# 20W-IR-Blaster.net
KiCad netlist of a schematic drawn in EAGLE
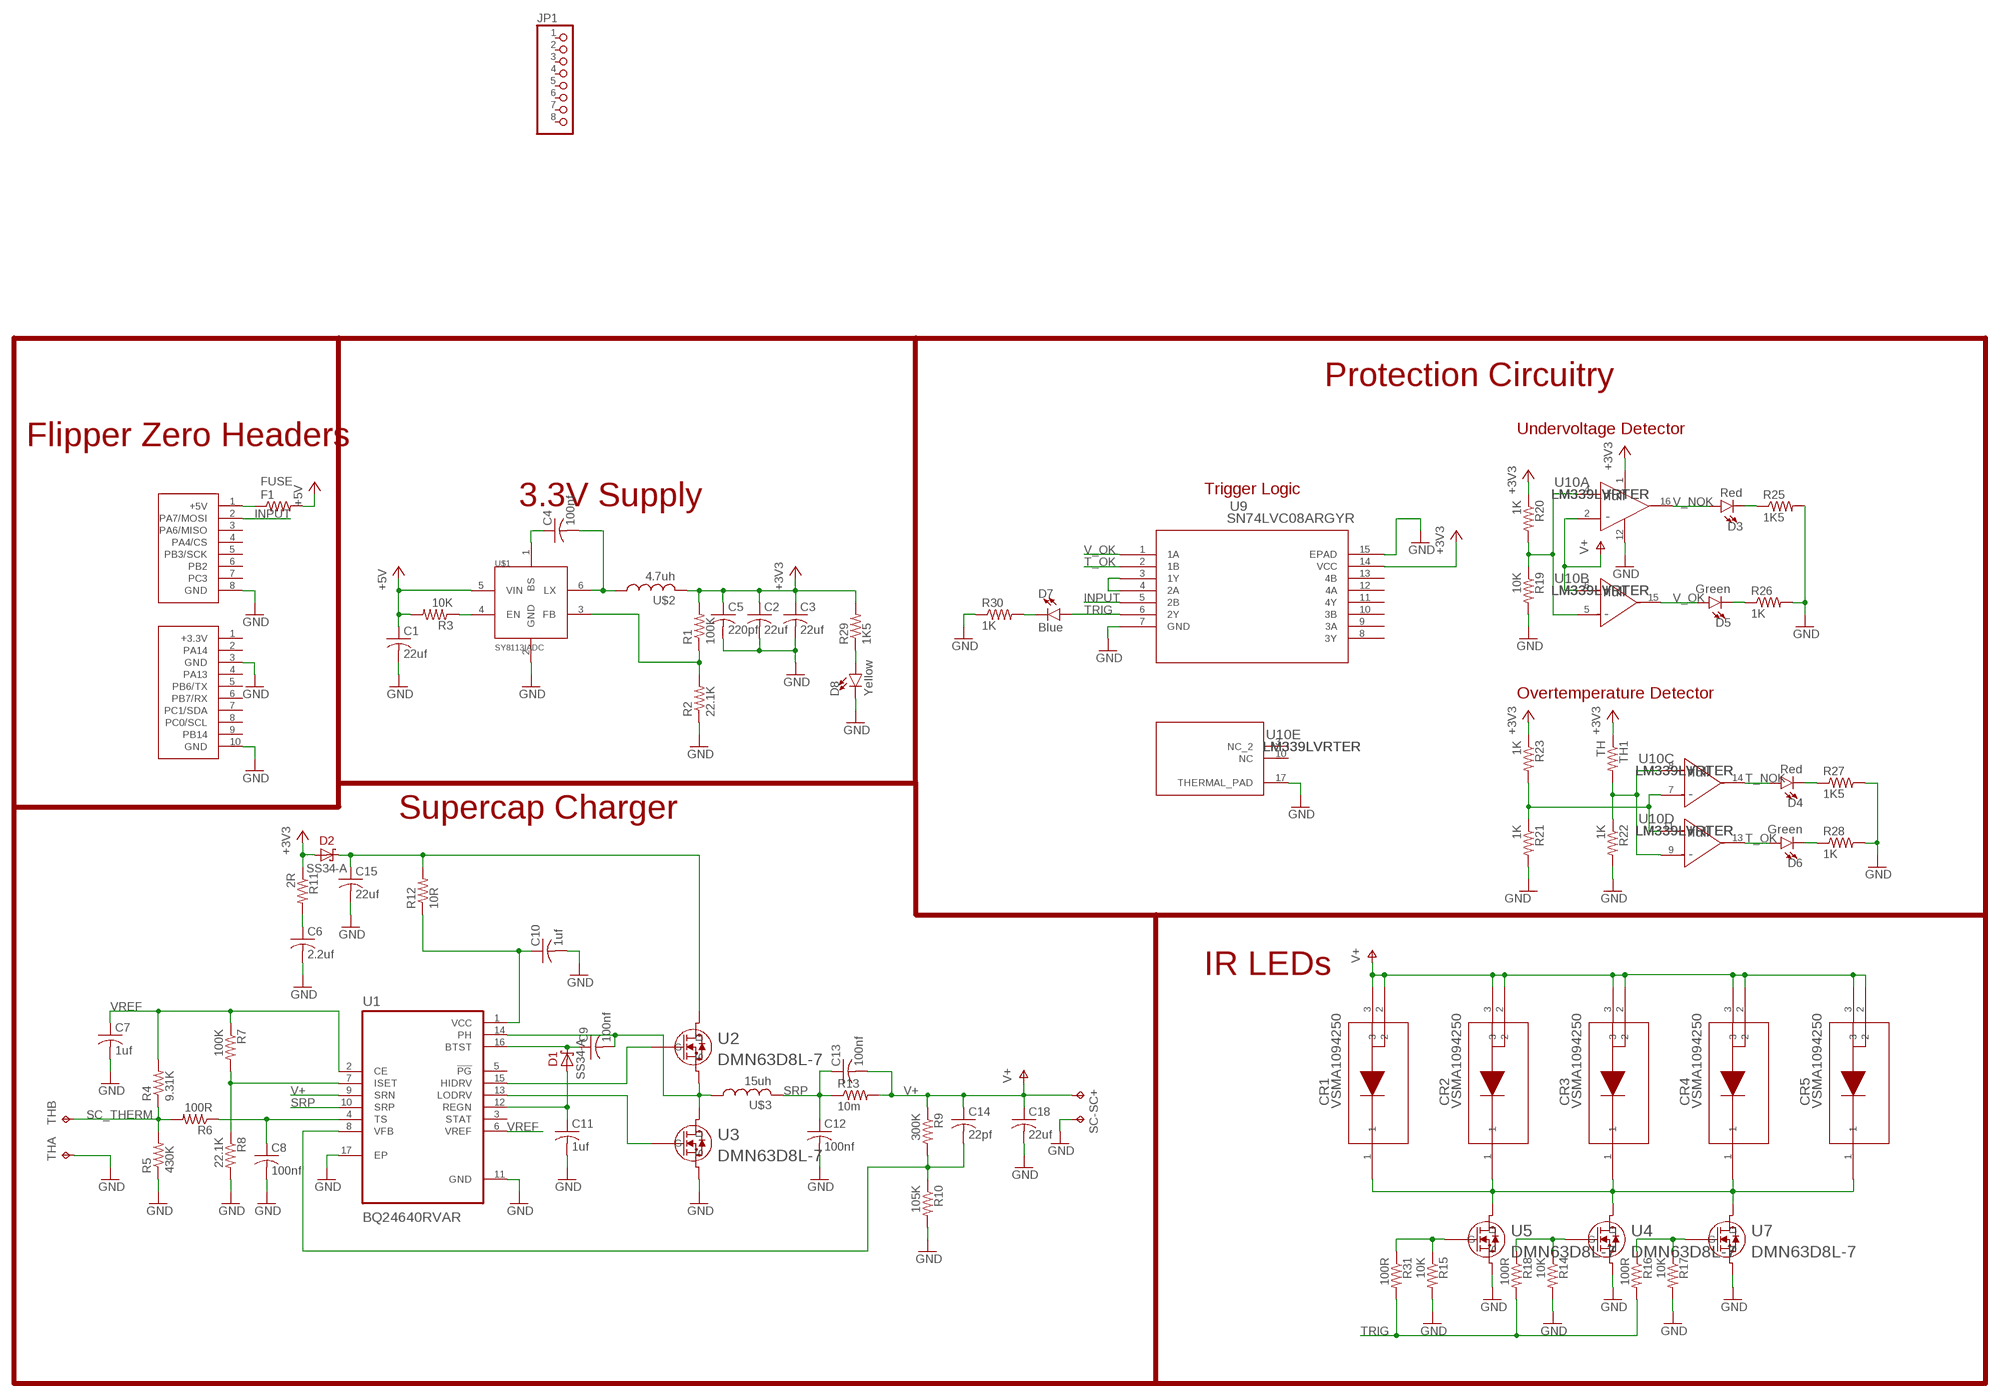
[diagram p0: schematic, sheet 1]

(export (version "E")
  (design (tool "Eeschema 10.0.6"))
  (components
    (comp (ref "C1")
      (value "22uf")
      (footprint "eagle-import:C3216")
      (libsource (lib "eagle-import") (part "C-USC3216"))
    )
    (comp (ref "C2")
      (value "22uf")
      (footprint "eagle-import:C3216")
      (libsource (lib "eagle-import") (part "C-USC3216"))
    )
    (comp (ref "C3")
      (value "22uf")
      (footprint "eagle-import:C3216")
      (libsource (lib "eagle-import") (part "C-USC3216"))
    )
    (comp (ref "C4")
      (value "100nf")
      (footprint "eagle-import:C0603")
      (libsource (lib "eagle-import") (part "C-USC0603"))
    )
    (comp (ref "C5")
      (value "220pf")
      (footprint "eagle-import:C0603")
      (libsource (lib "eagle-import") (part "C-USC0603"))
    )
    (comp (ref "C6")
      (value "2.2uf")
      (footprint "eagle-import:C0603")
      (libsource (lib "eagle-import") (part "C-USC0603"))
    )
    (comp (ref "C7")
      (value "1uf")
      (footprint "eagle-import:C0603")
      (libsource (lib "eagle-import") (part "C-USC0603"))
    )
    (comp (ref "C8")
      (value "100nf")
      (footprint "eagle-import:C0603")
      (libsource (lib "eagle-import") (part "C-USC0603"))
    )
    (comp (ref "C9")
      (value "100nf")
      (footprint "eagle-import:C0603")
      (libsource (lib "eagle-import") (part "C-USC0603"))
    )
    (comp (ref "C10")
      (value "1uf")
      (footprint "eagle-import:C0603")
      (libsource (lib "eagle-import") (part "C-USC0603"))
    )
    (comp (ref "C11")
      (value "1uf")
      (footprint "eagle-import:C0603")
      (libsource (lib "eagle-import") (part "C-USC0603"))
    )
    (comp (ref "C12")
      (value "100nf")
      (footprint "eagle-import:C0603")
      (libsource (lib "eagle-import") (part "C-USC0603"))
    )
    (comp (ref "C13")
      (value "100nf")
      (footprint "eagle-import:C0603")
      (libsource (lib "eagle-import") (part "C-USC0603"))
    )
    (comp (ref "C14")
      (value "22pf")
      (footprint "eagle-import:C0603")
      (libsource (lib "eagle-import") (part "C-USC0603"))
    )
    (comp (ref "C15")
      (value "22uf")
      (footprint "eagle-import:C3216")
      (libsource (lib "eagle-import") (part "C-USC3216"))
    )
    (comp (ref "C18")
      (value "22uf")
      (footprint "eagle-import:C3216")
      (libsource (lib "eagle-import") (part "C-USC3216"))
    )
    (comp (ref "CR1")
      (value "VSMA1094250")
      (footprint "eagle-import:DIODE_VSMA1094250_VIS")
      (fields (field (name "COPYRIGHT") "Copyright (C) 2025 Ultra Librarian. All rights reserved."))
      (libsource (lib "eagle-import") (part "VSMA1094250"))
    )
    (comp (ref "CR2")
      (value "VSMA1094250")
      (footprint "eagle-import:DIODE_VSMA1094250_VIS")
      (fields (field (name "COPYRIGHT") "Copyright (C) 2025 Ultra Librarian. All rights reserved."))
      (libsource (lib "eagle-import") (part "VSMA1094250"))
    )
    (comp (ref "CR3")
      (value "VSMA1094250")
      (footprint "eagle-import:DIODE_VSMA1094250_VIS")
      (fields (field (name "COPYRIGHT") "Copyright (C) 2025 Ultra Librarian. All rights reserved."))
      (libsource (lib "eagle-import") (part "VSMA1094250"))
    )
    (comp (ref "CR4")
      (value "VSMA1094250")
      (footprint "eagle-import:DIODE_VSMA1094250_VIS")
      (fields (field (name "COPYRIGHT") "Copyright (C) 2025 Ultra Librarian. All rights reserved."))
      (libsource (lib "eagle-import") (part "VSMA1094250"))
    )
    (comp (ref "CR5")
      (value "VSMA1094250")
      (footprint "eagle-import:DIODE_VSMA1094250_VIS")
      (fields (field (name "COPYRIGHT") "Copyright (C) 2025 Ultra Librarian. All rights reserved."))
      (libsource (lib "eagle-import") (part "VSMA1094250"))
    )
    (comp (ref "D1")
      (value "SS34-A")
      (footprint "eagle-import:DO-214AC")
      (fields (field (name "MF") "TE Connectivity") (field (name "MP") "SS34A"))
      (libsource (lib "eagle-import") (part "SS34-A"))
    )
    (comp (ref "D2")
      (value "SS34-A")
      (footprint "eagle-import:DO-214AC")
      (fields (field (name "MF") "TE Connectivity") (field (name "MP") "SS34A"))
      (libsource (lib "eagle-import") (part "SS34-A"))
    )
    (comp (ref "D3")
      (value "Red")
      (footprint "eagle-import:LED-0603")
      (libsource (lib "eagle-import") (part "LED-RED0603"))
    )
    (comp (ref "D4")
      (value "Red")
      (footprint "eagle-import:LED-0603")
      (libsource (lib "eagle-import") (part "LED-RED0603"))
    )
    (comp (ref "D5")
      (value "Green")
      (footprint "eagle-import:LED-0603")
      (libsource (lib "eagle-import") (part "LED-GREEN0603"))
    )
    (comp (ref "D6")
      (value "Green")
      (footprint "eagle-import:LED-0603")
      (libsource (lib "eagle-import") (part "LED-GREEN0603"))
    )
    (comp (ref "D7")
      (value "Blue")
      (footprint "eagle-import:LED-0603")
      (libsource (lib "eagle-import") (part "LED-BLUE0603"))
    )
    (comp (ref "D8")
      (value "Yellow")
      (footprint "eagle-import:LED-0603")
      (libsource (lib "eagle-import") (part "LED-YELLOW0603"))
    )
    (comp (ref "F1")
      (value "FUSE")
      (footprint "eagle-import:R1206")
      (libsource (lib "eagle-import") (part "R-US_R1206"))
    )
    (comp (ref "JP1")
      (value "PINHD-1X8")
      (footprint "eagle-import:1X08")
      (libsource (lib "eagle-import") (part "PINHD-1X8"))
    )
    (comp (ref "R1")
      (value "100K")
      (footprint "eagle-import:R0603")
      (libsource (lib "eagle-import") (part "R-US_R0603"))
    )
    (comp (ref "R2")
      (value "22.1K")
      (footprint "eagle-import:R0603")
      (libsource (lib "eagle-import") (part "R-US_R0603"))
    )
    (comp (ref "R3")
      (value "10K")
      (footprint "eagle-import:R0603")
      (libsource (lib "eagle-import") (part "R-US_R0603"))
    )
    (comp (ref "R4")
      (value "9.31K")
      (footprint "eagle-import:R0603")
      (libsource (lib "eagle-import") (part "R-US_R0603"))
    )
    (comp (ref "R5")
      (value "430K")
      (footprint "eagle-import:R0603")
      (libsource (lib "eagle-import") (part "R-US_R0603"))
    )
    (comp (ref "R6")
      (value "100R")
      (footprint "eagle-import:R0603")
      (libsource (lib "eagle-import") (part "R-US_R0603"))
    )
    (comp (ref "R7")
      (value "100K")
      (footprint "eagle-import:R0603")
      (libsource (lib "eagle-import") (part "R-US_R0603"))
    )
    (comp (ref "R8")
      (value "22.1K")
      (footprint "eagle-import:R0603")
      (libsource (lib "eagle-import") (part "R-US_R0603"))
    )
    (comp (ref "R9")
      (value "300K")
      (footprint "eagle-import:R0603")
      (libsource (lib "eagle-import") (part "R-US_R0603"))
    )
    (comp (ref "R10")
      (value "105K")
      (footprint "eagle-import:R0603")
      (libsource (lib "eagle-import") (part "R-US_R0603"))
    )
    (comp (ref "R11")
      (value "2R")
      (footprint "eagle-import:R2512")
      (libsource (lib "eagle-import") (part "R-US_R2512"))
    )
    (comp (ref "R12")
      (value "10R")
      (footprint "eagle-import:R2512")
      (libsource (lib "eagle-import") (part "R-US_R2512"))
    )
    (comp (ref "R13")
      (value "10m")
      (footprint "eagle-import:R0805")
      (libsource (lib "eagle-import") (part "R-US_R0805"))
    )
    (comp (ref "R14")
      (value "10K")
      (footprint "eagle-import:R0603")
      (libsource (lib "eagle-import") (part "R-US_R0603"))
    )
    (comp (ref "R15")
      (value "10K")
      (footprint "eagle-import:R0603")
      (libsource (lib "eagle-import") (part "R-US_R0603"))
    )
    (comp (ref "R16")
      (value "100R")
      (footprint "eagle-import:R0603")
      (libsource (lib "eagle-import") (part "R-US_R0603"))
    )
    (comp (ref "R17")
      (value "10K")
      (footprint "eagle-import:R0603")
      (libsource (lib "eagle-import") (part "R-US_R0603"))
    )
    (comp (ref "R18")
      (value "100R")
      (footprint "eagle-import:R0603")
      (libsource (lib "eagle-import") (part "R-US_R0603"))
    )
    (comp (ref "R19")
      (value "10K")
      (footprint "eagle-import:R0603")
      (libsource (lib "eagle-import") (part "R-US_R0603"))
    )
    (comp (ref "R20")
      (value "1K")
      (footprint "eagle-import:R0603")
      (libsource (lib "eagle-import") (part "R-US_R0603"))
    )
    (comp (ref "R21")
      (value "1K")
      (footprint "eagle-import:R0603")
      (libsource (lib "eagle-import") (part "R-US_R0603"))
    )
    (comp (ref "R22")
      (value "1K")
      (footprint "eagle-import:R0603")
      (libsource (lib "eagle-import") (part "R-US_R0603"))
    )
    (comp (ref "R23")
      (value "1K")
      (footprint "eagle-import:R0603")
      (libsource (lib "eagle-import") (part "R-US_R0603"))
    )
    (comp (ref "R25")
      (value "1K5")
      (footprint "eagle-import:R0603")
      (libsource (lib "eagle-import") (part "R-US_R0603"))
    )
    (comp (ref "R26")
      (value "1K")
      (footprint "eagle-import:R0603")
      (libsource (lib "eagle-import") (part "R-US_R0603"))
    )
    (comp (ref "R27")
      (value "1K5")
      (footprint "eagle-import:R0603")
      (libsource (lib "eagle-import") (part "R-US_R0603"))
    )
    (comp (ref "R28")
      (value "1K")
      (footprint "eagle-import:R0603")
      (libsource (lib "eagle-import") (part "R-US_R0603"))
    )
    (comp (ref "R29")
      (value "1K5")
      (footprint "eagle-import:R0603")
      (libsource (lib "eagle-import") (part "R-US_R0603"))
    )
    (comp (ref "R30")
      (value "1K")
      (footprint "eagle-import:R0603")
      (libsource (lib "eagle-import") (part "R-US_R0603"))
    )
    (comp (ref "R31")
      (value "100R")
      (footprint "eagle-import:R0603")
      (libsource (lib "eagle-import") (part "R-US_R0603"))
    )
    (comp (ref "SC+")
      (value "TPPAD1-20Y")
      (footprint "eagle-import:P1-20Y")
      (libsource (lib "eagle-import") (part "TPPAD1-20Y"))
    )
    (comp (ref "SC-")
      (value "TPPAD1-20Y")
      (footprint "eagle-import:P1-20Y")
      (libsource (lib "eagle-import") (part "TPPAD1-20Y"))
    )
    (comp (ref "TH")
      (value "TP2P2-38-17")
      (footprint "eagle-import:P2-38-17")
      (libsource (lib "eagle-import") (part "TP2P2-38-17"))
    )
    (comp (ref "TH1")
      (value "TH")
      (footprint "eagle-import:R0603")
      (libsource (lib "eagle-import") (part "R-US_R0603"))
    )
    (comp (ref "U$1")
      (value "SY8113IADC")
      (footprint "eagle-import:TSOT6")
      (libsource (lib "eagle-import") (part "SY8113IADC"))
    )
    (comp (ref "U$2")
      (value "4.7uh")
      (footprint "eagle-import:CYH127-4.7UH")
      (libsource (lib "eagle-import") (part "CYH127-4.7UH"))
    )
    (comp (ref "U$3")
      (value "15uh")
      (footprint "eagle-import:CYH127-4.7UH")
      (libsource (lib "eagle-import") (part "CYH127-4.7UH"))
    )
    (comp (ref "U$4")
      (value "LEFT-H1-SMD")
      (footprint "eagle-import:LEFT-H1-SMD")
      (libsource (lib "eagle-import") (part "LEFT-H1-SMD"))
    )
    (comp (ref "U$5")
      (value "RIGHT-H2-SMD")
      (footprint "eagle-import:RIGHT-H2-SMD")
      (libsource (lib "eagle-import") (part "RIGHT-H2-SMD"))
    )
    (comp (ref "U1")
      (value "BQ24640RVAR")
      (footprint "eagle-import:QFN50P350X350X100-17N")
      (libsource (lib "eagle-import") (part "BQ24640RVAR"))
    )
    (comp (ref "U2")
      (value "DMN63D8L-7")
      (footprint "eagle-import:SOIC_63D8L-7_DIO")
      (fields (field (name "COPYRIGHT") "Copyright (C) 2025 Ultra Librarian. All rights reserved."))
      (libsource (lib "eagle-import") (part "DMN63D8L-7"))
    )
    (comp (ref "U3")
      (value "DMN63D8L-7")
      (footprint "eagle-import:SOIC_63D8L-7_DIO")
      (fields (field (name "COPYRIGHT") "Copyright (C) 2025 Ultra Librarian. All rights reserved."))
      (libsource (lib "eagle-import") (part "DMN63D8L-7"))
    )
    (comp (ref "U4")
      (value "DMN63D8L-7")
      (footprint "eagle-import:SOIC_63D8L-7_DIO")
      (fields (field (name "COPYRIGHT") "Copyright (C) 2025 Ultra Librarian. All rights reserved."))
      (libsource (lib "eagle-import") (part "DMN63D8L-7"))
    )
    (comp (ref "U5")
      (value "DMN63D8L-7")
      (footprint "eagle-import:SOIC_63D8L-7_DIO")
      (fields (field (name "COPYRIGHT") "Copyright (C) 2025 Ultra Librarian. All rights reserved."))
      (libsource (lib "eagle-import") (part "DMN63D8L-7"))
    )
    (comp (ref "U7")
      (value "DMN63D8L-7")
      (footprint "eagle-import:SOIC_63D8L-7_DIO")
      (fields (field (name "COPYRIGHT") "Copyright (C) 2025 Ultra Librarian. All rights reserved."))
      (libsource (lib "eagle-import") (part "DMN63D8L-7"))
    )
    (comp (ref "U9")
      (value "SN74LVC08ARGYR")
      (footprint "eagle-import:RGY14_2P05X2P05")
      (fields (field (name "COPYRIGHT") "Copyright (C) 2025 Ultra Librarian. All rights reserved."))
      (libsource (lib "eagle-import") (part "SN74LVC08ARGYR"))
    )
    (comp (ref "U10")
      (value "LM339LVRTER")
      (footprint "eagle-import:RTE0016C-IPC_A")
      (fields (field (name "COPYRIGHT") "Copyright (C) 2025 Ultra Librarian. All rights reserved."))
      (libsource (lib "eagle-import") (part "LM339LVRTER"))
    )
  )
  (nets
    (net (code "1") (name "+3V3") (class "Default")
      (node (ref "C2") (pin "1") (pinfunction "1_1") (pintype "passive"))
      (node (ref "C3") (pin "1") (pinfunction "1_1") (pintype "passive"))
      (node (ref "C5") (pin "1") (pinfunction "1_1") (pintype "passive"))
      (node (ref "D2") (pin "A") (pinfunction "A_A") (pintype "passive"))
      (node (ref "R1") (pin "2") (pinfunction "2_2") (pintype "passive"))
      (node (ref "R11") (pin "1") (pinfunction "1_1") (pintype "passive"))
      (node (ref "R20") (pin "1") (pinfunction "1_1") (pintype "passive"))
      (node (ref "R23") (pin "1") (pinfunction "1_1") (pintype "passive"))
      (node (ref "R29") (pin "2") (pinfunction "2_2") (pintype "passive"))
      (node (ref "TH1") (pin "1") (pinfunction "1_1") (pintype "passive"))
      (node (ref "U$2") (pin "P$2") (pinfunction "2_P$2") (pintype "passive"))
      (node (ref "U10") (pin "1") (pinfunction "V+_1") (pintype "power_in"))
      (node (ref "U9") (pin "14") (pinfunction "VCC_14") (pintype "power_in"))
    )
    (net (code "2") (name "+5V") (class "Default")
      (node (ref "C1") (pin "1") (pinfunction "1_1") (pintype "passive"))
      (node (ref "F1") (pin "2") (pinfunction "2_2") (pintype "passive"))
      (node (ref "R3") (pin "2") (pinfunction "2_2") (pintype "passive"))
      (node (ref "U$1") (pin "5") (pinfunction "VIN_5") (pintype "bidirectional"))
    )
    (net (code "3") (name "/INPUT") (class "Default")
      (node (ref "U$4") (pin "2") (pinfunction "PA7/MOSI_2") (pintype "bidirectional"))
      (node (ref "U9") (pin "5") (pinfunction "2B_5") (pintype "input"))
    )
    (net (code "4") (name "/SC_THERM") (class "Default")
      (node (ref "R4") (pin "1") (pinfunction "1_1") (pintype "passive"))
      (node (ref "R5") (pin "2") (pinfunction "2_2") (pintype "passive"))
      (node (ref "R6") (pin "2") (pinfunction "2_2") (pintype "passive"))
      (node (ref "TH") (pin "TP-2") (pinfunction "TP_TP-2") (pintype "input"))
    )
    (net (code "5") (name "/SRP") (class "Default")
      (node (ref "C12") (pin "1") (pinfunction "1_1") (pintype "passive"))
      (node (ref "C13") (pin "1") (pinfunction "1_1") (pintype "passive"))
      (node (ref "R13") (pin "1") (pinfunction "1_1") (pintype "passive"))
      (node (ref "U$3") (pin "P$2") (pinfunction "2_P$2") (pintype "passive"))
      (node (ref "U1") (pin "10") (pinfunction "SRP_10") (pintype "input"))
    )
    (net (code "6") (name "/TRIG") (class "Default")
      (node (ref "D7") (pin "A") (pinfunction "A_A") (pintype "passive"))
      (node (ref "R16") (pin "2") (pinfunction "2_2") (pintype "passive"))
      (node (ref "R18") (pin "2") (pinfunction "2_2") (pintype "passive"))
      (node (ref "R31") (pin "2") (pinfunction "2_2") (pintype "passive"))
      (node (ref "U9") (pin "6") (pinfunction "2Y_6") (pintype "output"))
    )
    (net (code "7") (name "/T_NOK") (class "Default")
      (node (ref "D4") (pin "A") (pinfunction "A_A") (pintype "passive"))
      (node (ref "U10") (pin "14") (pinfunction "OUT3_14") (pintype "passive"))
    )
    (net (code "8") (name "/T_OK") (class "Default")
      (node (ref "D6") (pin "A") (pinfunction "A_A") (pintype "passive"))
      (node (ref "U10") (pin "13") (pinfunction "OUT4_13") (pintype "passive"))
      (node (ref "U9") (pin "2") (pinfunction "1B_2") (pintype "input"))
    )
    (net (code "9") (name "/VREF") (class "Default")
      (node (ref "C7") (pin "1") (pinfunction "1_1") (pintype "passive"))
      (node (ref "R4") (pin "2") (pinfunction "2_2") (pintype "passive"))
      (node (ref "R7") (pin "1") (pinfunction "1_1") (pintype "passive"))
      (node (ref "U1") (pin "2") (pinfunction "CE_2") (pintype "input"))
      (node (ref "U1") (pin "6") (pinfunction "VREF_6") (pintype "output"))
    )
    (net (code "10") (name "/V_NOK") (class "Default")
      (node (ref "D3") (pin "A") (pinfunction "A_A") (pintype "passive"))
      (node (ref "U10") (pin "16") (pinfunction "OUT1_16") (pintype "passive"))
    )
    (net (code "11") (name "/V_OK") (class "Default")
      (node (ref "D5") (pin "A") (pinfunction "A_A") (pintype "passive"))
      (node (ref "U10") (pin "15") (pinfunction "OUT2_15") (pintype "passive"))
      (node (ref "U9") (pin "1") (pinfunction "1A_1") (pintype "input"))
    )
    (net (code "12") (name "GND") (class "Default")
      (node (ref "C1") (pin "2") (pinfunction "2_2") (pintype "passive"))
      (node (ref "C10") (pin "2") (pinfunction "2_2") (pintype "passive"))
      (node (ref "C11") (pin "2") (pinfunction "2_2") (pintype "passive"))
      (node (ref "C12") (pin "2") (pinfunction "2_2") (pintype "passive"))
      (node (ref "C15") (pin "2") (pinfunction "2_2") (pintype "passive"))
      (node (ref "C18") (pin "2") (pinfunction "2_2") (pintype "passive"))
      (node (ref "C2") (pin "2") (pinfunction "2_2") (pintype "passive"))
      (node (ref "C3") (pin "2") (pinfunction "2_2") (pintype "passive"))
      (node (ref "C5") (pin "2") (pinfunction "2_2") (pintype "passive"))
      (node (ref "C6") (pin "2") (pinfunction "2_2") (pintype "passive"))
      (node (ref "C7") (pin "2") (pinfunction "2_2") (pintype "passive"))
      (node (ref "C8") (pin "2") (pinfunction "2_2") (pintype "passive"))
      (node (ref "D8") (pin "C") (pinfunction "C_C") (pintype "passive"))
      (node (ref "R10") (pin "2") (pinfunction "2_2") (pintype "passive"))
      (node (ref "R14") (pin "2") (pinfunction "2_2") (pintype "passive"))
      (node (ref "R15") (pin "2") (pinfunction "2_2") (pintype "passive"))
      (node (ref "R17") (pin "2") (pinfunction "2_2") (pintype "passive"))
      (node (ref "R19") (pin "2") (pinfunction "2_2") (pintype "passive"))
      (node (ref "R2") (pin "1") (pinfunction "1_1") (pintype "passive"))
      (node (ref "R21") (pin "2") (pinfunction "2_2") (pintype "passive"))
      (node (ref "R22") (pin "2") (pinfunction "2_2") (pintype "passive"))
      (node (ref "R25") (pin "2") (pinfunction "2_2") (pintype "passive"))
      (node (ref "R26") (pin "2") (pinfunction "2_2") (pintype "passive"))
      (node (ref "R27") (pin "2") (pinfunction "2_2") (pintype "passive"))
      (node (ref "R28") (pin "2") (pinfunction "2_2") (pintype "passive"))
      (node (ref "R30") (pin "1") (pinfunction "1_1") (pintype "passive"))
      (node (ref "R5") (pin "1") (pinfunction "1_1") (pintype "passive"))
      (node (ref "R8") (pin "2") (pinfunction "2_2") (pintype "passive"))
      (node (ref "SC-") (pin "TP") (pinfunction "TP_TP") (pintype "input"))
      (node (ref "TH") (pin "TP-1") (pinfunction "TP_TP-1") (pintype "input"))
      (node (ref "U$1") (pin "2") (pinfunction "GND_2") (pintype "bidirectional"))
      (node (ref "U$4") (pin "8") (pinfunction "GND_8") (pintype "bidirectional"))
      (node (ref "U$5") (pin "10") (pinfunction "GND_10") (pintype "bidirectional"))
      (node (ref "U$5") (pin "3") (pinfunction "GND_3") (pintype "bidirectional"))
      (node (ref "U1") (pin "11") (pinfunction "GND_11") (pintype "power_in"))
      (node (ref "U1") (pin "17") (pinfunction "EP_17") (pintype "bidirectional"))
      (node (ref "U10") (pin "12") (pinfunction "GND_12") (pintype "power_in"))
      (node (ref "U10") (pin "17") (pinfunction "THERMAL_PAD_17") (pintype "passive"))
      (node (ref "U3") (pin "3") (pinfunction "S_3") (pintype "passive"))
      (node (ref "U4") (pin "3") (pinfunction "S_3") (pintype "passive"))
      (node (ref "U5") (pin "3") (pinfunction "S_3") (pintype "passive"))
      (node (ref "U7") (pin "3") (pinfunction "S_3") (pintype "passive"))
      (node (ref "U9") (pin "15") (pinfunction "EPAD_15") (pintype "passive"))
      (node (ref "U9") (pin "7") (pinfunction "GND_7") (pintype "power_in"))
    )
    (net (code "13") (name "Net-(C6-Pad1)") (class "Default")
      (node (ref "C6") (pin "1") (pinfunction "1_1") (pintype "passive"))
      (node (ref "R11") (pin "2") (pinfunction "2_2") (pintype "passive"))
    )
    (net (code "14") (name "Net-(D3-PadC)") (class "Default")
      (node (ref "D3") (pin "C") (pinfunction "C_C") (pintype "passive"))
      (node (ref "R25") (pin "1") (pinfunction "1_1") (pintype "passive"))
    )
    (net (code "15") (name "Net-(D4-PadC)") (class "Default")
      (node (ref "D4") (pin "C") (pinfunction "C_C") (pintype "passive"))
      (node (ref "R27") (pin "1") (pinfunction "1_1") (pintype "passive"))
    )
    (net (code "16") (name "Net-(D5-PadC)") (class "Default")
      (node (ref "D5") (pin "C") (pinfunction "C_C") (pintype "passive"))
      (node (ref "R26") (pin "1") (pinfunction "1_1") (pintype "passive"))
    )
    (net (code "17") (name "Net-(D6-PadC)") (class "Default")
      (node (ref "D6") (pin "C") (pinfunction "C_C") (pintype "passive"))
      (node (ref "R28") (pin "1") (pinfunction "1_1") (pintype "passive"))
    )
    (net (code "18") (name "Net-(D7-PadC)") (class "Default")
      (node (ref "D7") (pin "C") (pinfunction "C_C") (pintype "passive"))
      (node (ref "R30") (pin "2") (pinfunction "2_2") (pintype "passive"))
    )
    (net (code "19") (name "Net-(D8-PadA)") (class "Default")
      (node (ref "D8") (pin "A") (pinfunction "A_A") (pintype "passive"))
      (node (ref "R29") (pin "1") (pinfunction "1_1") (pintype "passive"))
    )
    (net (code "20") (name "Net-(U$1-BS)") (class "Default")
      (node (ref "C4") (pin "1") (pinfunction "1_1") (pintype "passive"))
      (node (ref "U$1") (pin "1") (pinfunction "BS_1") (pintype "bidirectional"))
    )
    (net (code "21") (name "Net-(U$1-EN)") (class "Default")
      (node (ref "R3") (pin "1") (pinfunction "1_1") (pintype "passive"))
      (node (ref "U$1") (pin "4") (pinfunction "EN_4") (pintype "bidirectional"))
    )
    (net (code "22") (name "Net-(U$1-FB)") (class "Default")
      (node (ref "R1") (pin "1") (pinfunction "1_1") (pintype "passive"))
      (node (ref "R2") (pin "2") (pinfunction "2_2") (pintype "passive"))
      (node (ref "U$1") (pin "3") (pinfunction "FB_3") (pintype "bidirectional"))
    )
    (net (code "23") (name "Net-(U$1-LX)") (class "Default")
      (node (ref "C4") (pin "2") (pinfunction "2_2") (pintype "passive"))
      (node (ref "U$1") (pin "6") (pinfunction "LX_6") (pintype "bidirectional"))
      (node (ref "U$2") (pin "P$1") (pinfunction "1_P$1") (pintype "passive"))
    )
    (net (code "24") (name "Net-(U$3-1)") (class "Default")
      (node (ref "C9") (pin "2") (pinfunction "2_2") (pintype "passive"))
      (node (ref "U$3") (pin "P$1") (pinfunction "1_P$1") (pintype "passive"))
      (node (ref "U1") (pin "14") (pinfunction "PH_14") (pintype "power_in"))
      (node (ref "U2") (pin "3") (pinfunction "S_3") (pintype "passive"))
      (node (ref "U3") (pin "2") (pinfunction "D_2") (pintype "passive"))
    )
    (net (code "25") (name "Net-(U$4-+5V)") (class "Default")
      (node (ref "F1") (pin "1") (pinfunction "1_1") (pintype "passive"))
      (node (ref "U$4") (pin "1") (pinfunction "+5V_1") (pintype "bidirectional"))
    )
    (net (code "26") (name "Net-(U1-BTST)") (class "Default")
      (node (ref "C9") (pin "1") (pinfunction "1_1") (pintype "passive"))
      (node (ref "D1") (pin "C") (pinfunction "C_C") (pintype "passive"))
      (node (ref "U1") (pin "16") (pinfunction "BTST_16") (pintype "power_in"))
    )
    (net (code "27") (name "Net-(U1-HIDRV)") (class "Default")
      (node (ref "U1") (pin "15") (pinfunction "HIDRV_15") (pintype "output"))
      (node (ref "U2") (pin "1") (pinfunction "G_1") (pintype "passive"))
    )
    (net (code "28") (name "Net-(U1-ISET)") (class "Default")
      (node (ref "R7") (pin "2") (pinfunction "2_2") (pintype "passive"))
      (node (ref "R8") (pin "1") (pinfunction "1_1") (pintype "passive"))
      (node (ref "U1") (pin "7") (pinfunction "ISET_7") (pintype "input"))
    )
    (net (code "29") (name "Net-(U1-LODRV)") (class "Default")
      (node (ref "U1") (pin "13") (pinfunction "LODRV_13") (pintype "output"))
      (node (ref "U3") (pin "1") (pinfunction "G_1") (pintype "passive"))
    )
    (net (code "30") (name "Net-(U1-REGN)") (class "Default")
      (node (ref "C11") (pin "1") (pinfunction "1_1") (pintype "passive"))
      (node (ref "D1") (pin "A") (pinfunction "A_A") (pintype "passive"))
      (node (ref "U1") (pin "12") (pinfunction "REGN_12") (pintype "output"))
    )
    (net (code "31") (name "Net-(U1-TS)") (class "Default")
      (node (ref "C8") (pin "1") (pinfunction "1_1") (pintype "passive"))
      (node (ref "R6") (pin "1") (pinfunction "1_1") (pintype "passive"))
      (node (ref "U1") (pin "4") (pinfunction "TS_4") (pintype "input"))
    )
    (net (code "32") (name "Net-(U1-VCC)") (class "Default")
      (node (ref "C10") (pin "1") (pinfunction "1_1") (pintype "passive"))
      (node (ref "R12") (pin "1") (pinfunction "1_1") (pintype "passive"))
      (node (ref "U1") (pin "1") (pinfunction "VCC_1") (pintype "power_in"))
    )
    (net (code "33") (name "Net-(U1-VFB)") (class "Default")
      (node (ref "C14") (pin "2") (pinfunction "2_2") (pintype "passive"))
      (node (ref "R10") (pin "1") (pinfunction "1_1") (pintype "passive"))
      (node (ref "R9") (pin "2") (pinfunction "2_2") (pintype "passive"))
      (node (ref "U1") (pin "8") (pinfunction "VFB_8") (pintype "input"))
    )
    (net (code "34") (name "Net-(U2-D)") (class "Default")
      (node (ref "C15") (pin "1") (pinfunction "1_1") (pintype "passive"))
      (node (ref "D2") (pin "C") (pinfunction "C_C") (pintype "passive"))
      (node (ref "R12") (pin "2") (pinfunction "2_2") (pintype "passive"))
      (node (ref "U2") (pin "2") (pinfunction "D_2") (pintype "passive"))
    )
    (net (code "35") (name "Net-(U4-D)") (class "Default")
      (node (ref "CR1") (pin "1") (pinfunction "1_1") (pintype "passive"))
      (node (ref "CR2") (pin "1") (pinfunction "1_1") (pintype "passive"))
      (node (ref "CR3") (pin "1") (pinfunction "1_1") (pintype "passive"))
      (node (ref "CR4") (pin "1") (pinfunction "1_1") (pintype "passive"))
      (node (ref "CR5") (pin "1") (pinfunction "1_1") (pintype "passive"))
      (node (ref "U4") (pin "2") (pinfunction "D_2") (pintype "passive"))
      (node (ref "U5") (pin "2") (pinfunction "D_2") (pintype "passive"))
      (node (ref "U7") (pin "2") (pinfunction "D_2") (pintype "passive"))
    )
    (net (code "36") (name "Net-(U4-G)") (class "Default")
      (node (ref "R14") (pin "1") (pinfunction "1_1") (pintype "passive"))
      (node (ref "R18") (pin "1") (pinfunction "1_1") (pintype "passive"))
      (node (ref "U4") (pin "1") (pinfunction "G_1") (pintype "passive"))
    )
    (net (code "37") (name "Net-(U5-G)") (class "Default")
      (node (ref "R15") (pin "1") (pinfunction "1_1") (pintype "passive"))
      (node (ref "R31") (pin "1") (pinfunction "1_1") (pintype "passive"))
      (node (ref "U5") (pin "1") (pinfunction "G_1") (pintype "passive"))
    )
    (net (code "38") (name "Net-(U7-G)") (class "Default")
      (node (ref "R16") (pin "1") (pinfunction "1_1") (pintype "passive"))
      (node (ref "R17") (pin "1") (pinfunction "1_1") (pintype "passive"))
      (node (ref "U7") (pin "1") (pinfunction "G_1") (pintype "passive"))
    )
    (net (code "39") (name "Net-(U9-1Y)") (class "Default")
      (node (ref "U9") (pin "3") (pinfunction "1Y_3") (pintype "output"))
      (node (ref "U9") (pin "4") (pinfunction "2A_4") (pintype "input"))
    )
    (net (code "40") (name "Net-(U10A-IN1+)") (class "Default")
      (node (ref "R19") (pin "1") (pinfunction "1_1") (pintype "passive"))
      (node (ref "R20") (pin "2") (pinfunction "2_2") (pintype "passive"))
      (node (ref "U10") (pin "4") (pinfunction "IN1+_4") (pintype "tri_state"))
      (node (ref "U10") (pin "5") (pinfunction "IN2-_5") (pintype "tri_state"))
    )
    (net (code "41") (name "Net-(U10C-IN3+)") (class "Default")
      (node (ref "R22") (pin "1") (pinfunction "1_1") (pintype "passive"))
      (node (ref "TH1") (pin "2") (pinfunction "2_2") (pintype "passive"))
      (node (ref "U10") (pin "8") (pinfunction "IN3+_8") (pintype "tri_state"))
      (node (ref "U10") (pin "9") (pinfunction "IN4-_9") (pintype "tri_state"))
    )
    (net (code "42") (name "Net-(U10C-IN3-)") (class "Default")
      (node (ref "R21") (pin "1") (pinfunction "1_1") (pintype "passive"))
      (node (ref "R23") (pin "2") (pinfunction "2_2") (pintype "passive"))
      (node (ref "U10") (pin "11") (pinfunction "IN4+_11") (pintype "tri_state"))
      (node (ref "U10") (pin "7") (pinfunction "IN3-_7") (pintype "tri_state"))
    )
    (net (code "43") (name "V+") (class "Default")
      (node (ref "C13") (pin "2") (pinfunction "2_2") (pintype "passive"))
      (node (ref "C14") (pin "1") (pinfunction "1_1") (pintype "passive"))
      (node (ref "C18") (pin "1") (pinfunction "1_1") (pintype "passive"))
      (node (ref "CR1") (pin "2") (pinfunction "2_2") (pintype "passive"))
      (node (ref "CR1") (pin "3") (pinfunction "3_3") (pintype "passive"))
      (node (ref "CR2") (pin "2") (pinfunction "2_2") (pintype "passive"))
      (node (ref "CR2") (pin "3") (pinfunction "3_3") (pintype "passive"))
      (node (ref "CR3") (pin "2") (pinfunction "2_2") (pintype "passive"))
      (node (ref "CR3") (pin "3") (pinfunction "3_3") (pintype "passive"))
      (node (ref "CR4") (pin "2") (pinfunction "2_2") (pintype "passive"))
      (node (ref "CR4") (pin "3") (pinfunction "3_3") (pintype "passive"))
      (node (ref "CR5") (pin "2") (pinfunction "2_2") (pintype "passive"))
      (node (ref "CR5") (pin "3") (pinfunction "3_3") (pintype "passive"))
      (node (ref "R13") (pin "2") (pinfunction "2_2") (pintype "passive"))
      (node (ref "R9") (pin "1") (pinfunction "1_1") (pintype "passive"))
      (node (ref "SC+") (pin "TP") (pinfunction "TP_TP") (pintype "input"))
      (node (ref "U1") (pin "9") (pinfunction "SRN_9") (pintype "input"))
      (node (ref "U10") (pin "2") (pinfunction "IN1-_2") (pintype "tri_state"))
      (node (ref "U10") (pin "6") (pinfunction "IN2+_6") (pintype "tri_state"))
    )
    (net (code "44") (name "unconnected-(JP1-Pad1)") (class "Default")
      (node (ref "JP1") (pin "1") (pinfunction "1_1") (pintype "passive"))
    )
    (net (code "45") (name "unconnected-(JP1-Pad2)") (class "Default")
      (node (ref "JP1") (pin "2") (pinfunction "2_2") (pintype "passive"))
    )
    (net (code "46") (name "unconnected-(JP1-Pad3)") (class "Default")
      (node (ref "JP1") (pin "3") (pinfunction "3_3") (pintype "passive"))
    )
    (net (code "47") (name "unconnected-(JP1-Pad4)") (class "Default")
      (node (ref "JP1") (pin "4") (pinfunction "4_4") (pintype "passive"))
    )
    (net (code "48") (name "unconnected-(JP1-Pad5)") (class "Default")
      (node (ref "JP1") (pin "5") (pinfunction "5_5") (pintype "passive"))
    )
    (net (code "49") (name "unconnected-(JP1-Pad6)") (class "Default")
      (node (ref "JP1") (pin "6") (pinfunction "6_6") (pintype "passive"))
    )
    (net (code "50") (name "unconnected-(JP1-Pad7)") (class "Default")
      (node (ref "JP1") (pin "7") (pinfunction "7_7") (pintype "passive"))
    )
    (net (code "51") (name "unconnected-(JP1-Pad8)") (class "Default")
      (node (ref "JP1") (pin "8") (pinfunction "8_8") (pintype "passive"))
    )
    (net (code "52") (name "unconnected-(U$4-PA4{slash}CS-Pad4)") (class "Default")
      (node (ref "U$4") (pin "4") (pinfunction "PA4/CS_4") (pintype "bidirectional"))
    )
    (net (code "53") (name "unconnected-(U$4-PA6{slash}MISO-Pad3)") (class "Default")
      (node (ref "U$4") (pin "3") (pinfunction "PA6/MISO_3") (pintype "bidirectional"))
    )
    (net (code "54") (name "unconnected-(U$4-PB2-Pad6)") (class "Default")
      (node (ref "U$4") (pin "6") (pinfunction "PB2_6") (pintype "bidirectional"))
    )
    (net (code "55") (name "unconnected-(U$4-PB3{slash}SCK-Pad5)") (class "Default")
      (node (ref "U$4") (pin "5") (pinfunction "PB3/SCK_5") (pintype "bidirectional"))
    )
    (net (code "56") (name "unconnected-(U$4-PC3-Pad7)") (class "Default")
      (node (ref "U$4") (pin "7") (pinfunction "PC3_7") (pintype "bidirectional"))
    )
    (net (code "57") (name "unconnected-(U$5-+3.3V-Pad1)") (class "Default")
      (node (ref "U$5") (pin "1") (pinfunction "+3.3V_1") (pintype "bidirectional"))
    )
    (net (code "58") (name "unconnected-(U$5-PA13-Pad4)") (class "Default")
      (node (ref "U$5") (pin "4") (pinfunction "PA13_4") (pintype "bidirectional"))
    )
    (net (code "59") (name "unconnected-(U$5-PA14-Pad2)") (class "Default")
      (node (ref "U$5") (pin "2") (pinfunction "PA14_2") (pintype "bidirectional"))
    )
    (net (code "60") (name "unconnected-(U$5-PB6{slash}TX-Pad5)") (class "Default")
      (node (ref "U$5") (pin "5") (pinfunction "PB6/TX_5") (pintype "bidirectional"))
    )
    (net (code "61") (name "unconnected-(U$5-PB7{slash}RX-Pad6)") (class "Default")
      (node (ref "U$5") (pin "6") (pinfunction "PB7/RX_6") (pintype "bidirectional"))
    )
    (net (code "62") (name "unconnected-(U$5-PB14-Pad9)") (class "Default")
      (node (ref "U$5") (pin "9") (pinfunction "PB14_9") (pintype "bidirectional"))
    )
    (net (code "63") (name "unconnected-(U$5-PC0{slash}SCL-Pad8)") (class "Default")
      (node (ref "U$5") (pin "8") (pinfunction "PC0/SCL_8") (pintype "bidirectional"))
    )
    (net (code "64") (name "unconnected-(U$5-PC1{slash}SDA-Pad7)") (class "Default")
      (node (ref "U$5") (pin "7") (pinfunction "PC1/SDA_7") (pintype "bidirectional"))
    )
    (net (code "65") (name "unconnected-(U1-STAT-Pad3)") (class "Default")
      (node (ref "U1") (pin "3") (pinfunction "STAT_3") (pintype "output"))
    )
    (net (code "66") (name "unconnected-(U1-~{PG}-Pad5)") (class "Default")
      (node (ref "U1") (pin "5") (pinfunction "~{PG}_5") (pintype "output"))
    )
    (net (code "67") (name "unconnected-(U9-3A-Pad9)") (class "Default")
      (node (ref "U9") (pin "9") (pinfunction "3A_9") (pintype "input"))
    )
    (net (code "68") (name "unconnected-(U9-3B-Pad10)") (class "Default")
      (node (ref "U9") (pin "10") (pinfunction "3B_10") (pintype "input"))
    )
    (net (code "69") (name "unconnected-(U9-3Y-Pad8)") (class "Default")
      (node (ref "U9") (pin "8") (pinfunction "3Y_8") (pintype "output"))
    )
    (net (code "70") (name "unconnected-(U9-4A-Pad12)") (class "Default")
      (node (ref "U9") (pin "12") (pinfunction "4A_12") (pintype "input"))
    )
    (net (code "71") (name "unconnected-(U9-4B-Pad13)") (class "Default")
      (node (ref "U9") (pin "13") (pinfunction "4B_13") (pintype "input"))
    )
    (net (code "72") (name "unconnected-(U9-4Y-Pad11)") (class "Default")
      (node (ref "U9") (pin "11") (pinfunction "4Y_11") (pintype "output"))
    )
    (net (code "73") (name "unconnected-(U10E-NC-Pad10)") (class "Default")
      (node (ref "U10") (pin "10") (pinfunction "NC_10") (pintype "passive"))
    )
    (net (code "74") (name "unconnected-(U10E-NC_2-Pad3)") (class "Default")
      (node (ref "U10") (pin "3") (pinfunction "NC_2_3") (pintype "passive"))
    )
  )
)
